# Latch.net
KiCad netlist of a schematic drawn in Altium Designer
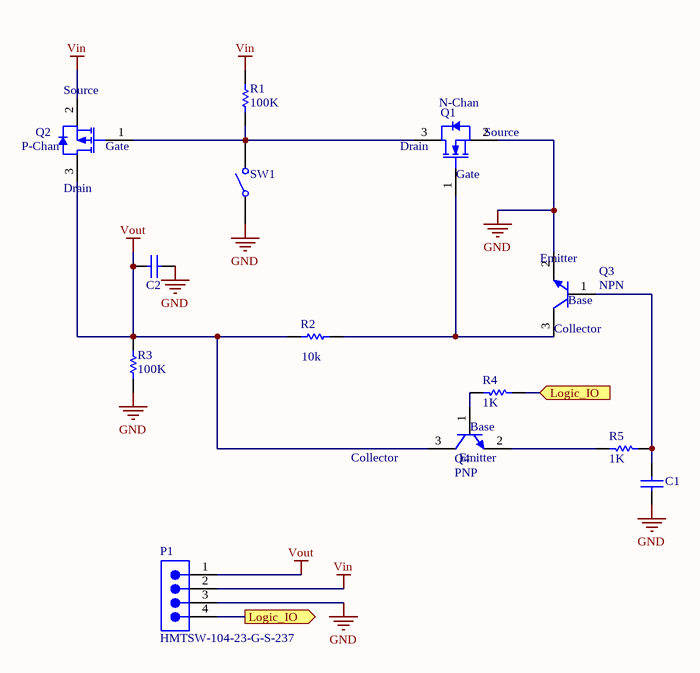
[diagram p0: Latch.SchDoc]

(export (version "E")
  (design (tool "Eeschema 10.0.6"))
  (components
    (comp (ref "C1")
      (value "CAP 100nF 6.3V 0603(1608)")
      (footprint "CAPC0603(1608)100_L")
      (description "CAP 100nF 6.3V ±20% 0603 (1608 Metric) Thickness 1mm SMD")
      (fields (field (name "TOLERANCE") "Â±20%"))
      (libsource (lib "Altium Content Vault") (part "CAP"))
    )
    (comp (ref "C2")
      (value "CAP 100nF 6.3V 0603(1608)")
      (footprint "CAPC0603(1608)100_L")
      (description "CAP 100nF 6.3V ±20% 0603 (1608 Metric) Thickness 1mm SMD")
      (fields (field (name "TOLERANCE") "Â±20%"))
      (libsource (lib "Altium Content Vault") (part "CAP"))
    )
    (comp (ref "P1")
      (value "HMTSW-104-23-G-S-237")
      (footprint "SMTC-HMTSW-104-23-X-S-237")
      (fields (field (name "MANUFACTURER") "Samtec"))
      (libsource (lib "Altium Content Vault") (part "SMTC-HMTSW-104-23-X-S-237"))
    )
    (comp (ref "Q1")
      (value "N-Chan")
      (footprint "ONSC-SOT-23-3-318-08_V")
      (description "MGSF2N02ELT1G Power MOSFET, 2.8 A, 20 V, N-Channel, 3-Pin SOT-23, Pb-Free, Tape and Reel")
      (fields (field (name "PARTNUMBER") "MGSF2N02ELT1G") (field (name "MANUFACTURER") "On Semiconductor"))
      (libsource (lib "Altium Content Vault") (part "ONSC-NMOS-G1S2D3-3"))
    )
    (comp (ref "Q2")
      (value "P-Chan")
      (footprint "AO-SOT-23-3L_V")
      (description "AO3401A P-Channel MOSFET, 30 V, 4 A, -55 to 150 degC, 3-Pin SOT-23-3L, RoHS, Tape and Reel")
      (fields (field (name "MANUFACTURER") "Alpha and Omega"))
      (libsource (lib "Altium Content Vault") (part "PEMOS-GSD-3"))
    )
    (comp (ref "Q3")
      (value "NPN")
      (footprint "ONSC-SC-70-3-419-04_V")
      (description "SMMBT2222AWT1GGeneral Purpose Transistor, NPN Silicon, 3-Pin SC70, Pb-Free, Tape and Reel")
      (fields (field (name "PARTNUMBER") "SMMBT2222AWT1G") (field (name "MANUFACTURER") "On Semiconductor"))
      (libsource (lib "Altium Content Vault") (part "ONSC-NPN-B1E2C3-3"))
    )
    (comp (ref "Q4")
      (value "PNP")
      (footprint "ONSC-SC-70-3-419-04_V")
      (description "MMBT3906WT1 General Purpose Transistor, PNP Silicon, 3-Pin SC70, Tape and Reel")
      (fields (field (name "PARTNUMBER") "MMBT3906WT1") (field (name "MANUFACTURER") "On Semiconductor"))
      (libsource (lib "Altium Content Vault") (part "ONSC-NPN-B1E2C3-3"))
    )
    (comp (ref "R1")
      (value "100K")
      (footprint "RESC0603(1608)_N")
      (description "100K 0.1W 1% 0603 (1608 Metric)  SMD")
      (fields (field (name "POWER") "0.1 W") (field (name "TOLERANCE") "1 %"))
      (libsource (lib "Altium Content Vault") (part "RES"))
    )
    (comp (ref "R2")
      (value "10k")
      (footprint "RESC1609X55X30LL10T20")
      (description "10kΩ 1%CRCW060310K0FKEA")
      (fields (field (name "PARTNUMBER") "CRCW060310K0FKEA"))
      (libsource (lib "Altium Content Vault") (part "RES-2"))
    )
    (comp (ref "R3")
      (value "100K")
      (footprint "RESC0603(1608)_N")
      (description "100K 0.1W 1% 0603 (1608 Metric)  SMD")
      (fields (field (name "POWER") "0.1 W") (field (name "TOLERANCE") "1 %"))
      (libsource (lib "Altium Content Vault") (part "RES"))
    )
    (comp (ref "R4")
      (value "1K")
      (footprint "RESC0603(1608)_L")
      (description "1K 0.1W 5% 0603 (1608 Metric)  SMD")
      (fields (field (name "TOLERANCE") "5 %") (field (name "POWER") "0.1 W"))
      (libsource (lib "Altium Content Vault") (part "RES"))
    )
    (comp (ref "R5")
      (value "1K")
      (footprint "RESC0603(1608)_L")
      (description "1K 0.1W 5% 0603 (1608 Metric)  SMD")
      (fields (field (name "TOLERANCE") "5 %") (field (name "POWER") "0.1 W"))
      (libsource (lib "Altium Content Vault") (part "RES"))
    )
    (comp (ref "SW1")
      (value "434121025816")
      (footprint "434121025816")
      (description "WS-TASV SMD Tact Switch 6.0X3.8 mm")
      (fields (field (name "MANUFACTURER") "Wuerth Elektronik"))
      (libsource (lib "Altium Content Vault") (part "WE-TACT-SW-2"))
    )
  )
  (nets
    (net (code "1") (name "/Logic_IO") (class "Default")
      (node (ref "P1") (pin "4") (pinfunction "4_4") (pintype "passive"))
      (node (ref "R4") (pin "1") (pinfunction "1_1") (pintype "passive"))
    )
    (net (code "2") (name "GND") (class "Default")
      (node (ref "C1") (pin "1") (pinfunction "1_1") (pintype "passive"))
      (node (ref "C2") (pin "1") (pinfunction "1_1") (pintype "passive"))
      (node (ref "P1") (pin "3") (pinfunction "3_3") (pintype "passive"))
      (node (ref "Q1") (pin "2") (pinfunction "S_2") (pintype "passive"))
      (node (ref "Q3") (pin "2") (pinfunction "E_2") (pintype "passive"))
      (node (ref "R3") (pin "1") (pinfunction "1_1") (pintype "passive"))
      (node (ref "SW1") (pin "1") (pinfunction "1_1") (pintype "passive"))
    )
    (net (code "3") (name "Net-(Q1-D)") (class "Default")
      (node (ref "Q1") (pin "3") (pinfunction "D_3") (pintype "passive"))
      (node (ref "Q2") (pin "1") (pinfunction "GATE_1") (pintype "passive"))
      (node (ref "R1") (pin "1") (pinfunction "1_1") (pintype "passive"))
      (node (ref "SW1") (pin "2") (pinfunction "2_2") (pintype "passive"))
    )
    (net (code "4") (name "Net-(Q1-G)") (class "Default")
      (node (ref "Q1") (pin "1") (pinfunction "G_1") (pintype "passive"))
      (node (ref "Q3") (pin "3") (pinfunction "C_3") (pintype "passive"))
      (node (ref "R2") (pin "2") (pinfunction "2_2") (pintype "passive"))
    )
    (net (code "5") (name "Net-(Q3-B)") (class "Default")
      (node (ref "C1") (pin "2") (pinfunction "2_2") (pintype "passive"))
      (node (ref "Q3") (pin "1") (pinfunction "B_1") (pintype "passive"))
      (node (ref "R5") (pin "2") (pinfunction "2_2") (pintype "passive"))
    )
    (net (code "6") (name "Net-(Q4-B)") (class "Default")
      (node (ref "Q4") (pin "1") (pinfunction "B_1") (pintype "passive"))
      (node (ref "R4") (pin "2") (pinfunction "2_2") (pintype "passive"))
    )
    (net (code "7") (name "Net-(Q4-E)") (class "Default")
      (node (ref "Q4") (pin "2") (pinfunction "E_2") (pintype "passive"))
      (node (ref "R5") (pin "1") (pinfunction "1_1") (pintype "passive"))
    )
    (net (code "8") (name "Vin") (class "Default")
      (node (ref "P1") (pin "2") (pinfunction "2_2") (pintype "passive"))
      (node (ref "Q2") (pin "2") (pinfunction "SOURCE_2") (pintype "passive"))
      (node (ref "R1") (pin "2") (pinfunction "2_2") (pintype "passive"))
    )
    (net (code "9") (name "Vout") (class "Default")
      (node (ref "C2") (pin "2") (pinfunction "2_2") (pintype "passive"))
      (node (ref "P1") (pin "1") (pinfunction "1_1") (pintype "passive"))
      (node (ref "Q2") (pin "3") (pinfunction "DRAIN_3") (pintype "passive"))
      (node (ref "Q4") (pin "3") (pinfunction "C_3") (pintype "passive"))
      (node (ref "R2") (pin "1") (pinfunction "1_1") (pintype "passive"))
      (node (ref "R3") (pin "2") (pinfunction "2_2") (pintype "passive"))
    )
  )
)
